# 2_ATTINY_85_20SU.net
KiCad netlist of a schematic drawn in EAGLE
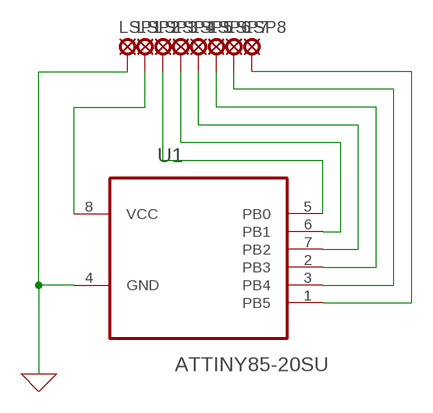
[diagram p0: schematic, sheet 1]

(export (version "E")
  (design (tool "Eeschema 10.0.6"))
  (components
    (comp (ref "LSP1")
      (value "LSP10_CLSP10_C")
      (footprint "eagle-import:LSP10_C")
      (libsource (lib "eagle-import") (part "LSP10_CLSP10_C"))
    )
    (comp (ref "LSP2")
      (value "LSP10_CLSP10_C")
      (footprint "eagle-import:LSP10_C")
      (libsource (lib "eagle-import") (part "LSP10_CLSP10_C"))
    )
    (comp (ref "LSP3")
      (value "LSP10_CLSP10_C")
      (footprint "eagle-import:LSP10_C")
      (libsource (lib "eagle-import") (part "LSP10_CLSP10_C"))
    )
    (comp (ref "LSP4")
      (value "LSP10_CLSP10_C")
      (footprint "eagle-import:LSP10_C")
      (libsource (lib "eagle-import") (part "LSP10_CLSP10_C"))
    )
    (comp (ref "LSP5")
      (value "LSP10_CLSP10_C")
      (footprint "eagle-import:LSP10_C")
      (libsource (lib "eagle-import") (part "LSP10_CLSP10_C"))
    )
    (comp (ref "LSP6")
      (value "LSP10_CLSP10_C")
      (footprint "eagle-import:LSP10_C")
      (libsource (lib "eagle-import") (part "LSP10_CLSP10_C"))
    )
    (comp (ref "LSP7")
      (value "LSP10_CLSP10_C")
      (footprint "eagle-import:LSP10_C")
      (libsource (lib "eagle-import") (part "LSP10_CLSP10_C"))
    )
    (comp (ref "LSP8")
      (value "LSP10_CLSP10_C")
      (footprint "eagle-import:LSP10_C")
      (libsource (lib "eagle-import") (part "LSP10_CLSP10_C"))
    )
    (comp (ref "U1")
      (value "ATTINY85-20SU")
      (footprint "eagle-import:SOIC127P798X216-8N")
      (fields (field (name "DIGI-KEY_PART_NUMBER") "ATTINY85-20SU-ND") (field (name "MF") "Microchip"))
      (libsource (lib "eagle-import") (part "ATTINY85-20SU"))
    )
  )
  (nets
    (net (code "1") (name "GND") (class "Default")
      (node (ref "LSP1") (pin "P$1") (pinfunction "MP_P$1") (pintype "passive"))
      (node (ref "U1") (pin "4") (pinfunction "GND_4") (pintype "passive"))
    )
    (net (code "2") (name "Net-(LSP2-MP)") (class "Default")
      (node (ref "LSP2") (pin "P$1") (pinfunction "MP_P$1") (pintype "passive"))
      (node (ref "U1") (pin "8") (pinfunction "VCC_8") (pintype "power_in"))
    )
    (net (code "3") (name "Net-(LSP3-MP)") (class "Default")
      (node (ref "LSP3") (pin "P$1") (pinfunction "MP_P$1") (pintype "passive"))
      (node (ref "U1") (pin "5") (pinfunction "PB0_5") (pintype "bidirectional"))
    )
    (net (code "4") (name "Net-(LSP4-MP)") (class "Default")
      (node (ref "LSP4") (pin "P$1") (pinfunction "MP_P$1") (pintype "passive"))
      (node (ref "U1") (pin "6") (pinfunction "PB1_6") (pintype "bidirectional"))
    )
    (net (code "5") (name "Net-(LSP5-MP)") (class "Default")
      (node (ref "LSP5") (pin "P$1") (pinfunction "MP_P$1") (pintype "passive"))
      (node (ref "U1") (pin "7") (pinfunction "PB2_7") (pintype "bidirectional"))
    )
    (net (code "6") (name "Net-(LSP6-MP)") (class "Default")
      (node (ref "LSP6") (pin "P$1") (pinfunction "MP_P$1") (pintype "passive"))
      (node (ref "U1") (pin "2") (pinfunction "PB3_2") (pintype "bidirectional"))
    )
    (net (code "7") (name "Net-(LSP7-MP)") (class "Default")
      (node (ref "LSP7") (pin "P$1") (pinfunction "MP_P$1") (pintype "passive"))
      (node (ref "U1") (pin "3") (pinfunction "PB4_3") (pintype "bidirectional"))
    )
    (net (code "8") (name "Net-(LSP8-MP)") (class "Default")
      (node (ref "LSP8") (pin "P$1") (pinfunction "MP_P$1") (pintype "passive"))
      (node (ref "U1") (pin "1") (pinfunction "PB5_1") (pintype "bidirectional"))
    )
  )
)
